# RS232.net
KiCad netlist of a schematic drawn in Altium Designer
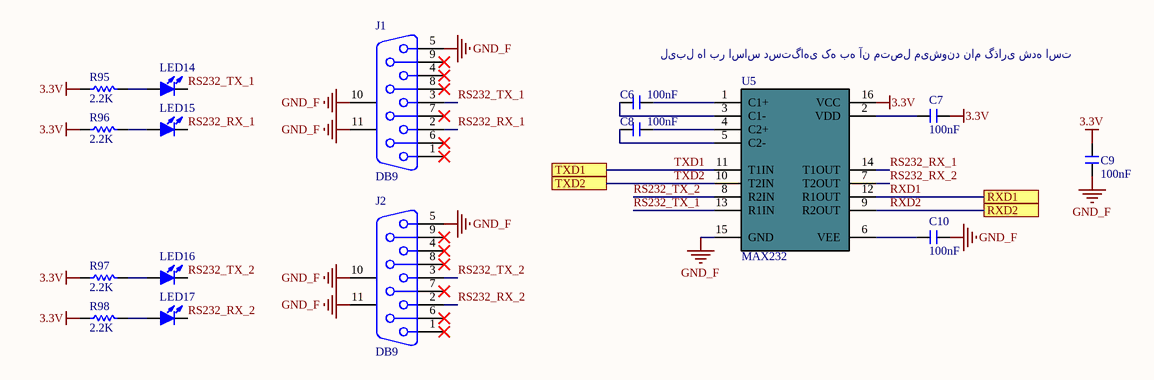
[diagram p0: RS232.SchDoc]

(export (version "E")
  (design (tool "Eeschema 10.0.6"))
  (components
    (comp (ref "C6")
      (value "100nF")
      (footprint "C 0805")
      (description "Non-polar patch capacitor")
      (fields (field (name "版权归属") "源创客"))
      (libsource (lib "Passive (Resistor-Capacitor-Inductor-Veristor-Ferrite)") (part "C"))
    )
    (comp (ref "C7")
      (value "100nF")
      (footprint "C 0805")
      (description "Non-polar patch capacitor")
      (fields (field (name "版权归属") "源创客"))
      (libsource (lib "Passive (Resistor-Capacitor-Inductor-Veristor-Ferrite)") (part "C"))
    )
    (comp (ref "C8")
      (value "100nF")
      (footprint "C 0805")
      (description "Non-polar patch capacitor")
      (fields (field (name "版权归属") "源创客"))
      (libsource (lib "Passive (Resistor-Capacitor-Inductor-Veristor-Ferrite)") (part "C"))
    )
    (comp (ref "C9")
      (value "100nF")
      (footprint "C 0805")
      (description "Non-polar patch capacitor")
      (fields (field (name "版权归属") "源创客"))
      (libsource (lib "Passive (Resistor-Capacitor-Inductor-Veristor-Ferrite)") (part "C"))
    )
    (comp (ref "C10")
      (value "100nF")
      (footprint "C 0805")
      (description "Non-polar patch capacitor")
      (fields (field (name "版权归属") "源创客"))
      (libsource (lib "Passive (Resistor-Capacitor-Inductor-Veristor-Ferrite)") (part "C"))
    )
    (comp (ref "J1")
      (value "DB9")
      (footprint "DB9/S_A")
      (description "9-pin serial port")
      (fields (field (name "版权归属") "源创客"))
      (libsource (lib "IO (Power-USB-Serial-VGA-RJ-Audio-Buzzer)") (part "DB9"))
    )
    (comp (ref "J2")
      (value "DB9")
      (footprint "DB9/S_A")
      (description "9-pin serial port")
      (fields (field (name "版权归属") "源创客"))
      (libsource (lib "IO (Power-USB-Serial-VGA-RJ-Audio-Buzzer)") (part "DB9"))
    )
    (comp (ref "LED14")
      (value "LED-SMD")
      (footprint "LED 0805Y")
      (description "Patch LED")
      (fields (field (name "版权归属") "源创客"))
      (libsource (lib "LED") (part "LED-SMD"))
    )
    (comp (ref "LED15")
      (value "LED-SMD")
      (footprint "LED 0805Y")
      (description "Patch LED")
      (fields (field (name "版权归属") "源创客"))
      (libsource (lib "LED") (part "LED-SMD"))
    )
    (comp (ref "LED16")
      (value "LED-SMD")
      (footprint "LED 0805Y")
      (description "Patch LED")
      (fields (field (name "版权归属") "源创客"))
      (libsource (lib "LED") (part "LED-SMD"))
    )
    (comp (ref "LED17")
      (value "LED-SMD")
      (footprint "LED 0805Y")
      (description "Patch LED")
      (fields (field (name "版权归属") "源创客"))
      (libsource (lib "LED") (part "LED-SMD"))
    )
    (comp (ref "R95")
      (value "2.2K")
      (footprint "R 0805")
      (description "Chip resistor")
      (fields (field (name "版权归属") "源创客"))
      (libsource (lib "Passive (Resistor-Capacitor-Inductor-Veristor-Ferrite)") (part "R"))
    )
    (comp (ref "R96")
      (value "2.2K")
      (footprint "R 0805")
      (description "Chip resistor")
      (fields (field (name "版权归属") "源创客"))
      (libsource (lib "Passive (Resistor-Capacitor-Inductor-Veristor-Ferrite)") (part "R"))
    )
    (comp (ref "R97")
      (value "2.2K")
      (footprint "R 0805")
      (description "Chip resistor")
      (fields (field (name "版权归属") "源创客"))
      (libsource (lib "Passive (Resistor-Capacitor-Inductor-Veristor-Ferrite)") (part "R"))
    )
    (comp (ref "R98")
      (value "2.2K")
      (footprint "R 0805")
      (description "Chip resistor")
      (fields (field (name "版权归属") "源创客"))
      (libsource (lib "Passive (Resistor-Capacitor-Inductor-Veristor-Ferrite)") (part "R"))
    )
    (comp (ref "U5")
      (value "MAX232")
      (footprint "SOP16_N")
      (description "RS432 to USB")
      (fields (field (name "版权归属") "源创客"))
      (libsource (lib "Integrated Circuit") (part "MAX232"))
    )
  )
  (nets
    (net (code "1") (name "/RS232_RX_1") (class "Default")
      (node (ref "J1") (pin "2") (pinfunction "2_2") (pintype "passive"))
      (node (ref "LED15") (pin "2") (pinfunction "K_2") (pintype "passive"))
      (node (ref "U5") (pin "14") (pinfunction "T1OUT_14") (pintype "passive"))
    )
    (net (code "2") (name "/RS232_RX_2") (class "Default")
      (node (ref "J2") (pin "2") (pinfunction "2_2") (pintype "passive"))
      (node (ref "LED17") (pin "2") (pinfunction "K_2") (pintype "passive"))
      (node (ref "U5") (pin "7") (pinfunction "T2OUT_7") (pintype "passive"))
    )
    (net (code "3") (name "/RS232_TX_1") (class "Default")
      (node (ref "J1") (pin "3") (pinfunction "3_3") (pintype "passive"))
      (node (ref "LED14") (pin "2") (pinfunction "K_2") (pintype "passive"))
      (node (ref "U5") (pin "13") (pinfunction "R1IN_13") (pintype "passive"))
    )
    (net (code "4") (name "/RS232_TX_2") (class "Default")
      (node (ref "J2") (pin "3") (pinfunction "3_3") (pintype "passive"))
      (node (ref "LED16") (pin "2") (pinfunction "K_2") (pintype "passive"))
      (node (ref "U5") (pin "8") (pinfunction "R2IN_8") (pintype "passive"))
    )
    (net (code "5") (name "/RXD1") (class "Default")
      (node (ref "U5") (pin "12") (pinfunction "R1OUT_12") (pintype "passive"))
    )
    (net (code "6") (name "/RXD2") (class "Default")
      (node (ref "U5") (pin "9") (pinfunction "R2OUT_9") (pintype "passive"))
    )
    (net (code "7") (name "/TXD1") (class "Default")
      (node (ref "U5") (pin "11") (pinfunction "T1IN_11") (pintype "passive"))
    )
    (net (code "8") (name "/TXD2") (class "Default")
      (node (ref "U5") (pin "10") (pinfunction "T2IN_10") (pintype "passive"))
    )
    (net (code "9") (name "3.3V") (class "Default")
      (node (ref "C7") (pin "2") (pinfunction "2_2") (pintype "passive"))
      (node (ref "C9") (pin "1") (pinfunction "1_1") (pintype "passive"))
      (node (ref "R95") (pin "1") (pinfunction "1_1") (pintype "passive"))
      (node (ref "R96") (pin "1") (pinfunction "1_1") (pintype "passive"))
      (node (ref "R97") (pin "1") (pinfunction "1_1") (pintype "passive"))
      (node (ref "R98") (pin "1") (pinfunction "1_1") (pintype "passive"))
      (node (ref "U5") (pin "16") (pinfunction "VCC_16") (pintype "passive"))
    )
    (net (code "10") (name "GND_F") (class "Default")
      (node (ref "C10") (pin "2") (pinfunction "2_2") (pintype "passive"))
      (node (ref "C9") (pin "2") (pinfunction "2_2") (pintype "passive"))
      (node (ref "J1") (pin "10") (pinfunction "MH1_10") (pintype "passive"))
      (node (ref "J1") (pin "11") (pinfunction "MH2_11") (pintype "passive"))
      (node (ref "J1") (pin "5") (pinfunction "5_5") (pintype "passive"))
      (node (ref "J2") (pin "10") (pinfunction "MH1_10") (pintype "passive"))
      (node (ref "J2") (pin "11") (pinfunction "MH2_11") (pintype "passive"))
      (node (ref "J2") (pin "5") (pinfunction "5_5") (pintype "passive"))
      (node (ref "U5") (pin "15") (pinfunction "GND_15") (pintype "passive"))
    )
    (net (code "11") (name "Net-(LED14-A)") (class "Default")
      (node (ref "LED14") (pin "1") (pinfunction "A_1") (pintype "passive"))
      (node (ref "R95") (pin "2") (pinfunction "2_2") (pintype "passive"))
    )
    (net (code "12") (name "Net-(LED15-A)") (class "Default")
      (node (ref "LED15") (pin "1") (pinfunction "A_1") (pintype "passive"))
      (node (ref "R96") (pin "2") (pinfunction "2_2") (pintype "passive"))
    )
    (net (code "13") (name "Net-(LED16-A)") (class "Default")
      (node (ref "LED16") (pin "1") (pinfunction "A_1") (pintype "passive"))
      (node (ref "R97") (pin "2") (pinfunction "2_2") (pintype "passive"))
    )
    (net (code "14") (name "Net-(LED17-A)") (class "Default")
      (node (ref "LED17") (pin "1") (pinfunction "A_1") (pintype "passive"))
      (node (ref "R98") (pin "2") (pinfunction "2_2") (pintype "passive"))
    )
    (net (code "15") (name "Net-(U5-C1+)") (class "Default")
      (node (ref "C6") (pin "2") (pinfunction "2_2") (pintype "passive"))
      (node (ref "U5") (pin "1") (pinfunction "C1+_1") (pintype "passive"))
    )
    (net (code "16") (name "Net-(U5-C1-)") (class "Default")
      (node (ref "C6") (pin "1") (pinfunction "1_1") (pintype "passive"))
      (node (ref "U5") (pin "3") (pinfunction "C1-_3") (pintype "passive"))
    )
    (net (code "17") (name "Net-(U5-C2+)") (class "Default")
      (node (ref "C8") (pin "1") (pinfunction "1_1") (pintype "passive"))
      (node (ref "U5") (pin "4") (pinfunction "C2+_4") (pintype "passive"))
    )
    (net (code "18") (name "Net-(U5-C2-)") (class "Default")
      (node (ref "C8") (pin "2") (pinfunction "2_2") (pintype "passive"))
      (node (ref "U5") (pin "5") (pinfunction "C2-_5") (pintype "passive"))
    )
    (net (code "19") (name "Net-(U5-VDD)") (class "Default")
      (node (ref "C7") (pin "1") (pinfunction "1_1") (pintype "passive"))
      (node (ref "U5") (pin "2") (pinfunction "VDD_2") (pintype "passive"))
    )
    (net (code "20") (name "Net-(U5-VEE)") (class "Default")
      (node (ref "C10") (pin "1") (pinfunction "1_1") (pintype "passive"))
      (node (ref "U5") (pin "6") (pinfunction "VEE_6") (pintype "passive"))
    )
    (net (code "21") (name "unconnected-(J1-Pad1)") (class "Default")
      (node (ref "J1") (pin "1") (pinfunction "1_1") (pintype "passive+no_connect"))
    )
    (net (code "22") (name "unconnected-(J1-Pad4)") (class "Default")
      (node (ref "J1") (pin "4") (pinfunction "4_4") (pintype "passive+no_connect"))
    )
    (net (code "23") (name "unconnected-(J1-Pad6)") (class "Default")
      (node (ref "J1") (pin "6") (pinfunction "6_6") (pintype "passive+no_connect"))
    )
    (net (code "24") (name "unconnected-(J1-Pad7)") (class "Default")
      (node (ref "J1") (pin "7") (pinfunction "7_7") (pintype "passive+no_connect"))
    )
    (net (code "25") (name "unconnected-(J1-Pad8)") (class "Default")
      (node (ref "J1") (pin "8") (pinfunction "8_8") (pintype "passive+no_connect"))
    )
    (net (code "26") (name "unconnected-(J1-Pad9)") (class "Default")
      (node (ref "J1") (pin "9") (pinfunction "9_9") (pintype "passive+no_connect"))
    )
    (net (code "27") (name "unconnected-(J2-Pad1)") (class "Default")
      (node (ref "J2") (pin "1") (pinfunction "1_1") (pintype "passive+no_connect"))
    )
    (net (code "28") (name "unconnected-(J2-Pad4)") (class "Default")
      (node (ref "J2") (pin "4") (pinfunction "4_4") (pintype "passive+no_connect"))
    )
    (net (code "29") (name "unconnected-(J2-Pad6)") (class "Default")
      (node (ref "J2") (pin "6") (pinfunction "6_6") (pintype "passive+no_connect"))
    )
    (net (code "30") (name "unconnected-(J2-Pad7)") (class "Default")
      (node (ref "J2") (pin "7") (pinfunction "7_7") (pintype "passive+no_connect"))
    )
    (net (code "31") (name "unconnected-(J2-Pad8)") (class "Default")
      (node (ref "J2") (pin "8") (pinfunction "8_8") (pintype "passive+no_connect"))
    )
    (net (code "32") (name "unconnected-(J2-Pad9)") (class "Default")
      (node (ref "J2") (pin "9") (pinfunction "9_9") (pintype "passive+no_connect"))
    )
  )
)
